# RE5Q_design_2.net
KiCad netlist of a schematic drawn in EasyEDA
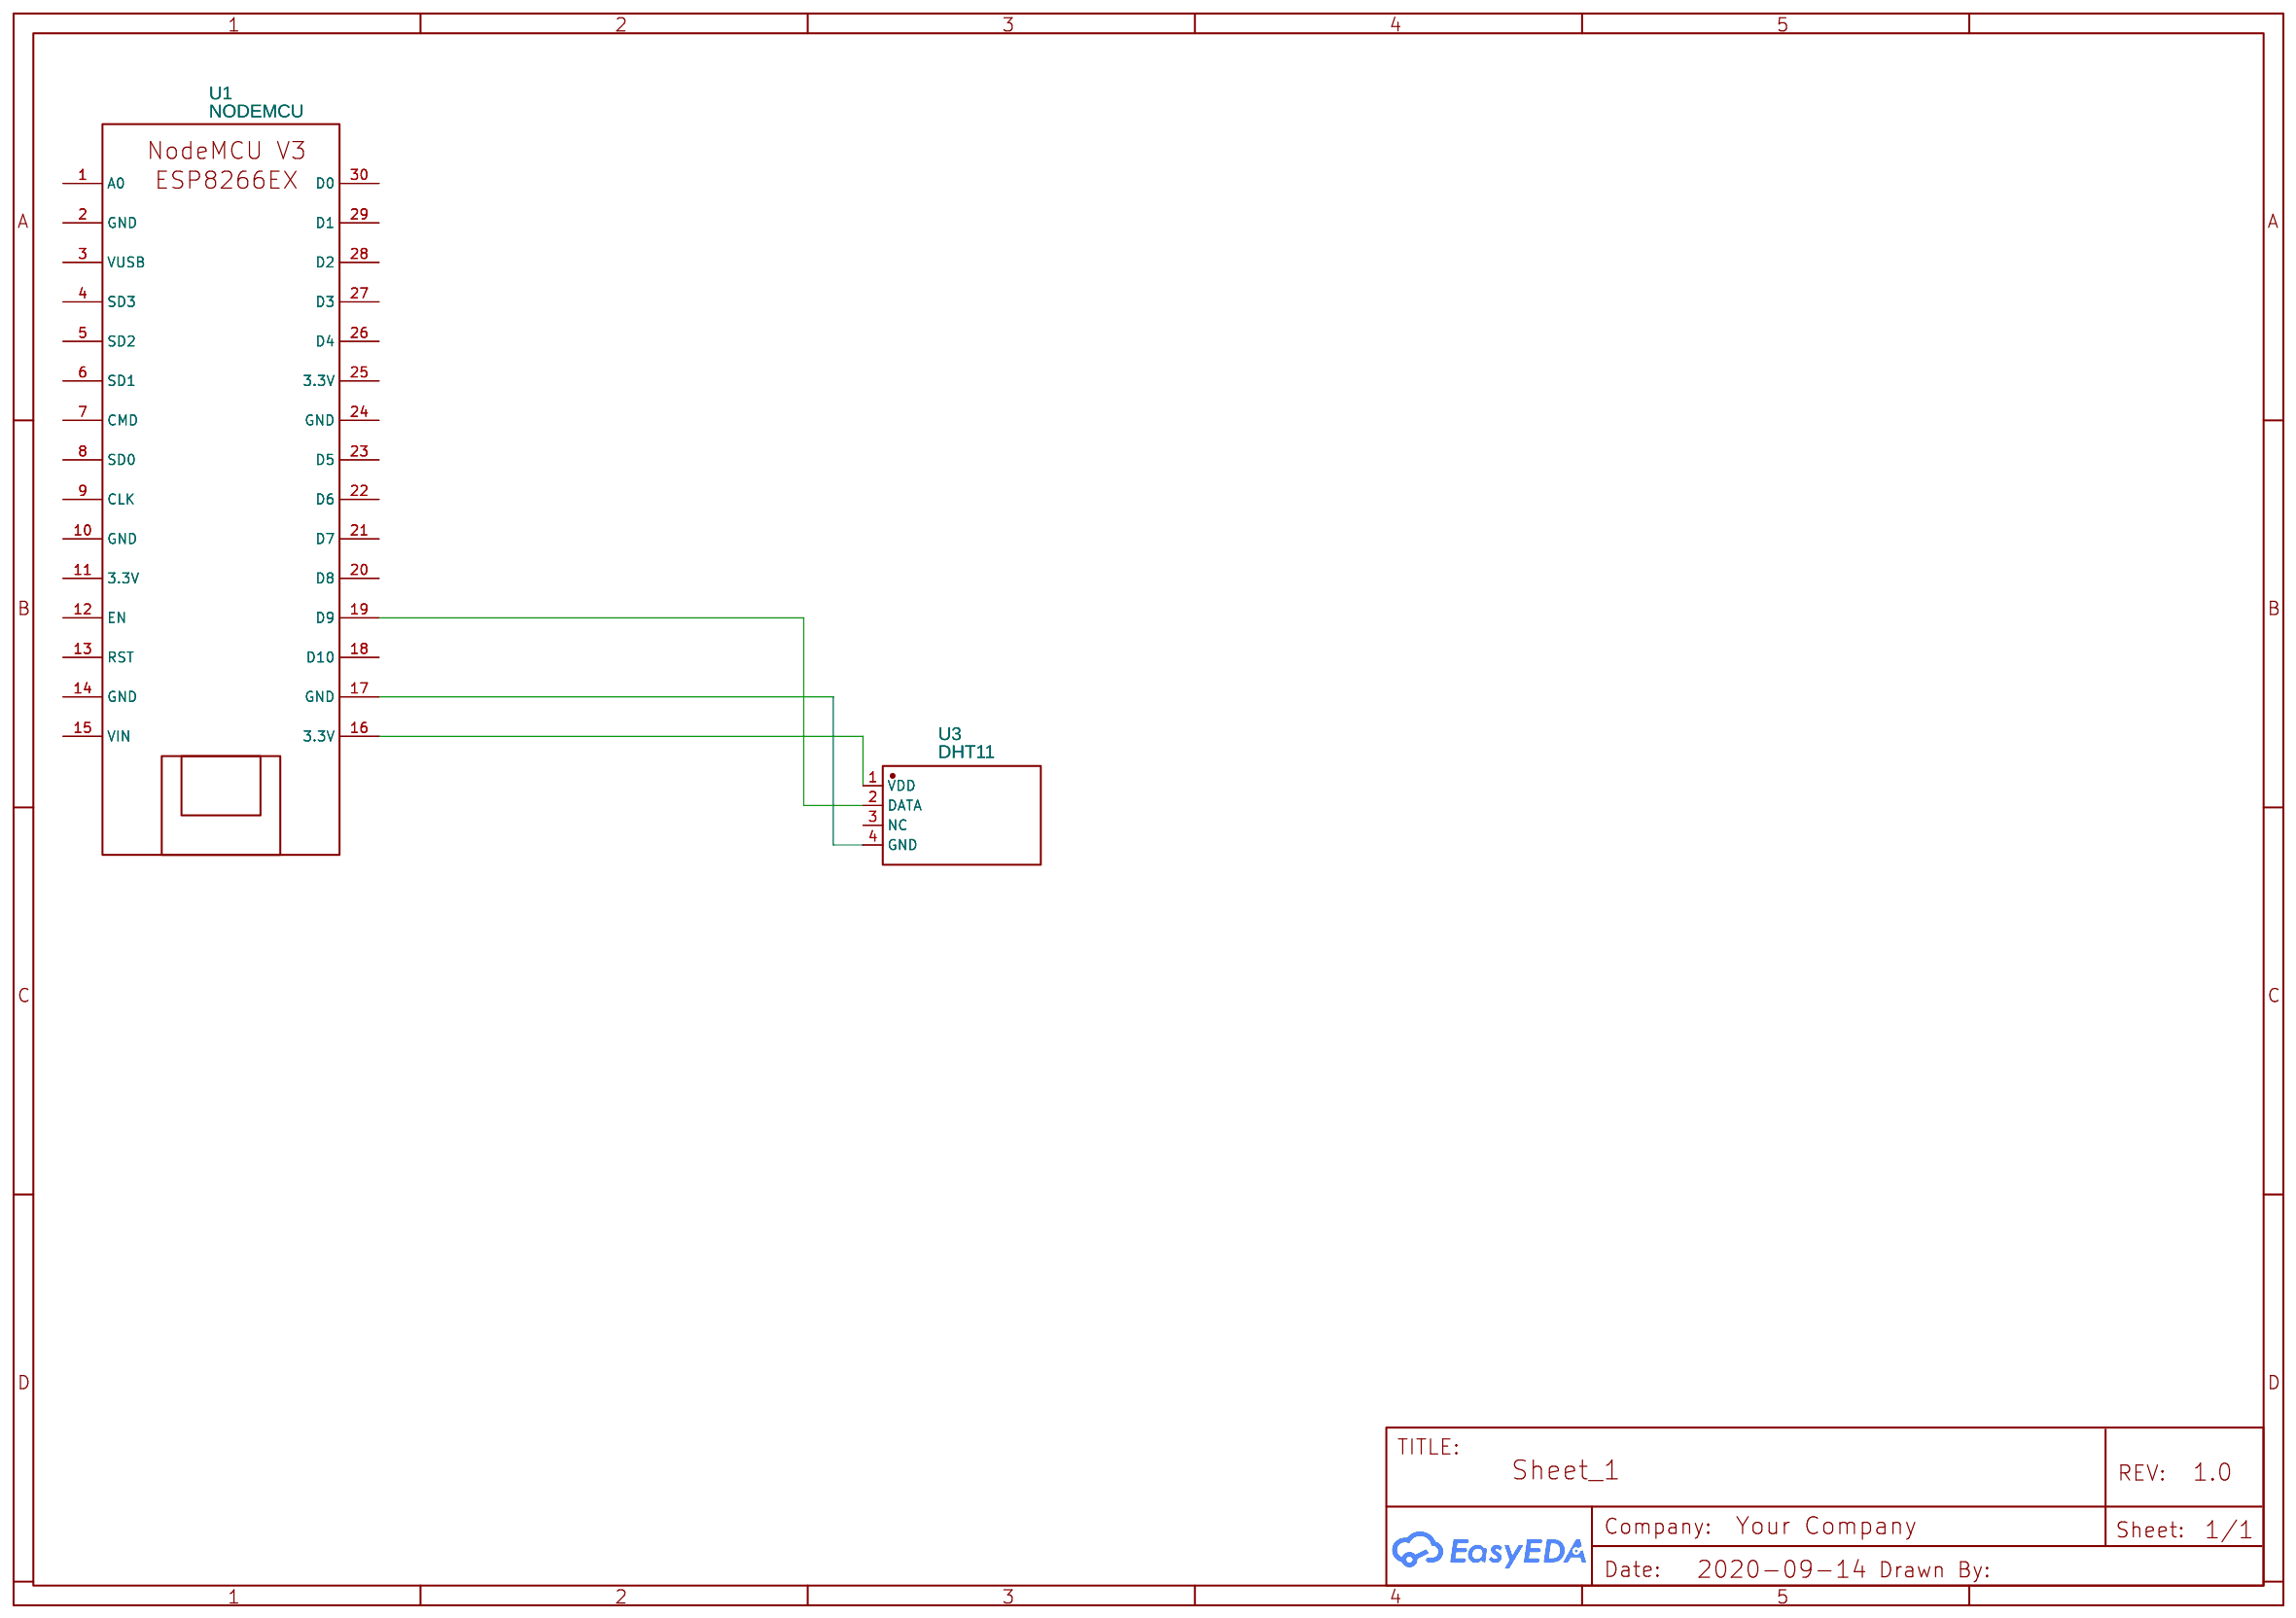
[diagram p0: schematic sheet]

(export (version "E")
  (design (tool "Eeschema 10.0.6"))
  (components
    (comp (ref "U1") (value "NODEMCU") (libsource (lib "") (part "NODEMCU")))
    (comp (ref "U3")
      (value "DHT11")
      (fields (field (name "BOM_Supplier Part") "C117051"))
      (libsource (lib "") (part "DHT11"))
    )
  )
  (nets
    (net (code "1") (name "Net-(U1-D9)") (class "Default")
      (node (ref "U1") (pin "19") (pinfunction "D9_19") (pintype "unspecified"))
      (node (ref "U3") (pin "2") (pinfunction "DATA_2") (pintype "unspecified"))
    )
    (net (code "2") (name "Net-(U3-GND)") (class "Default")
      (node (ref "U1") (pin "17") (pinfunction "GND_17") (pintype "unspecified"))
      (node (ref "U3") (pin "4") (pinfunction "GND_4") (pintype "unspecified"))
    )
    (net (code "3") (name "Net-(U3-VDD)") (class "Default")
      (node (ref "U1") (pin "16") (pinfunction "3.3V_16") (pintype "unspecified"))
      (node (ref "U3") (pin "1") (pinfunction "VDD_1") (pintype "unspecified"))
    )
    (net (code "4") (name "unconnected-(U1-3.3V-Pad11)") (class "Default")
      (node (ref "U1") (pin "11") (pinfunction "3.3V_11") (pintype "unspecified"))
    )
    (net (code "5") (name "unconnected-(U1-3.3V-Pad25)") (class "Default")
      (node (ref "U1") (pin "25") (pinfunction "3.3V_25") (pintype "unspecified"))
    )
    (net (code "6") (name "unconnected-(U1-A0-Pad1)") (class "Default")
      (node (ref "U1") (pin "1") (pinfunction "A0_1") (pintype "unspecified"))
    )
    (net (code "7") (name "unconnected-(U1-CLK-Pad9)") (class "Default")
      (node (ref "U1") (pin "9") (pinfunction "CLK_9") (pintype "unspecified"))
    )
    (net (code "8") (name "unconnected-(U1-CMD-Pad7)") (class "Default")
      (node (ref "U1") (pin "7") (pinfunction "CMD_7") (pintype "unspecified"))
    )
    (net (code "9") (name "unconnected-(U1-D0-Pad30)") (class "Default")
      (node (ref "U1") (pin "30") (pinfunction "D0_30") (pintype "unspecified"))
    )
    (net (code "10") (name "unconnected-(U1-D1-Pad29)") (class "Default")
      (node (ref "U1") (pin "29") (pinfunction "D1_29") (pintype "unspecified"))
    )
    (net (code "11") (name "unconnected-(U1-D2-Pad28)") (class "Default")
      (node (ref "U1") (pin "28") (pinfunction "D2_28") (pintype "unspecified"))
    )
    (net (code "12") (name "unconnected-(U1-D3-Pad27)") (class "Default")
      (node (ref "U1") (pin "27") (pinfunction "D3_27") (pintype "unspecified"))
    )
    (net (code "13") (name "unconnected-(U1-D4-Pad26)") (class "Default")
      (node (ref "U1") (pin "26") (pinfunction "D4_26") (pintype "unspecified"))
    )
    (net (code "14") (name "unconnected-(U1-D5-Pad23)") (class "Default")
      (node (ref "U1") (pin "23") (pinfunction "D5_23") (pintype "unspecified"))
    )
    (net (code "15") (name "unconnected-(U1-D6-Pad22)") (class "Default")
      (node (ref "U1") (pin "22") (pinfunction "D6_22") (pintype "unspecified"))
    )
    (net (code "16") (name "unconnected-(U1-D7-Pad21)") (class "Default")
      (node (ref "U1") (pin "21") (pinfunction "D7_21") (pintype "unspecified"))
    )
    (net (code "17") (name "unconnected-(U1-D8-Pad20)") (class "Default")
      (node (ref "U1") (pin "20") (pinfunction "D8_20") (pintype "unspecified"))
    )
    (net (code "18") (name "unconnected-(U1-D10-Pad18)") (class "Default")
      (node (ref "U1") (pin "18") (pinfunction "D10_18") (pintype "unspecified"))
    )
    (net (code "19") (name "unconnected-(U1-EN-Pad12)") (class "Default")
      (node (ref "U1") (pin "12") (pinfunction "EN_12") (pintype "unspecified"))
    )
    (net (code "20") (name "unconnected-(U1-GND-Pad2)") (class "Default")
      (node (ref "U1") (pin "2") (pinfunction "GND_2") (pintype "unspecified"))
    )
    (net (code "21") (name "unconnected-(U1-GND-Pad10)") (class "Default")
      (node (ref "U1") (pin "10") (pinfunction "GND_10") (pintype "unspecified"))
    )
    (net (code "22") (name "unconnected-(U1-GND-Pad14)") (class "Default")
      (node (ref "U1") (pin "14") (pinfunction "GND_14") (pintype "unspecified"))
    )
    (net (code "23") (name "unconnected-(U1-GND-Pad24)") (class "Default")
      (node (ref "U1") (pin "24") (pinfunction "GND_24") (pintype "unspecified"))
    )
    (net (code "24") (name "unconnected-(U1-RST-Pad13)") (class "Default")
      (node (ref "U1") (pin "13") (pinfunction "RST_13") (pintype "unspecified"))
    )
    (net (code "25") (name "unconnected-(U1-SD0-Pad8)") (class "Default")
      (node (ref "U1") (pin "8") (pinfunction "SD0_8") (pintype "unspecified"))
    )
    (net (code "26") (name "unconnected-(U1-SD1-Pad6)") (class "Default")
      (node (ref "U1") (pin "6") (pinfunction "SD1_6") (pintype "unspecified"))
    )
    (net (code "27") (name "unconnected-(U1-SD2-Pad5)") (class "Default")
      (node (ref "U1") (pin "5") (pinfunction "SD2_5") (pintype "unspecified"))
    )
    (net (code "28") (name "unconnected-(U1-SD3-Pad4)") (class "Default")
      (node (ref "U1") (pin "4") (pinfunction "SD3_4") (pintype "unspecified"))
    )
    (net (code "29") (name "unconnected-(U1-VIN-Pad15)") (class "Default")
      (node (ref "U1") (pin "15") (pinfunction "VIN_15") (pintype "unspecified"))
    )
    (net (code "30") (name "unconnected-(U1-VUSB-Pad3)") (class "Default")
      (node (ref "U1") (pin "3") (pinfunction "VUSB_3") (pintype "unspecified"))
    )
    (net (code "31") (name "unconnected-(U3-NC-Pad3)") (class "Default")
      (node (ref "U3") (pin "3") (pinfunction "NC_3") (pintype "unspecified"))
    )
  )
)
